# arduino_Uno_ref.net
KiCad netlist of a schematic drawn in EAGLE
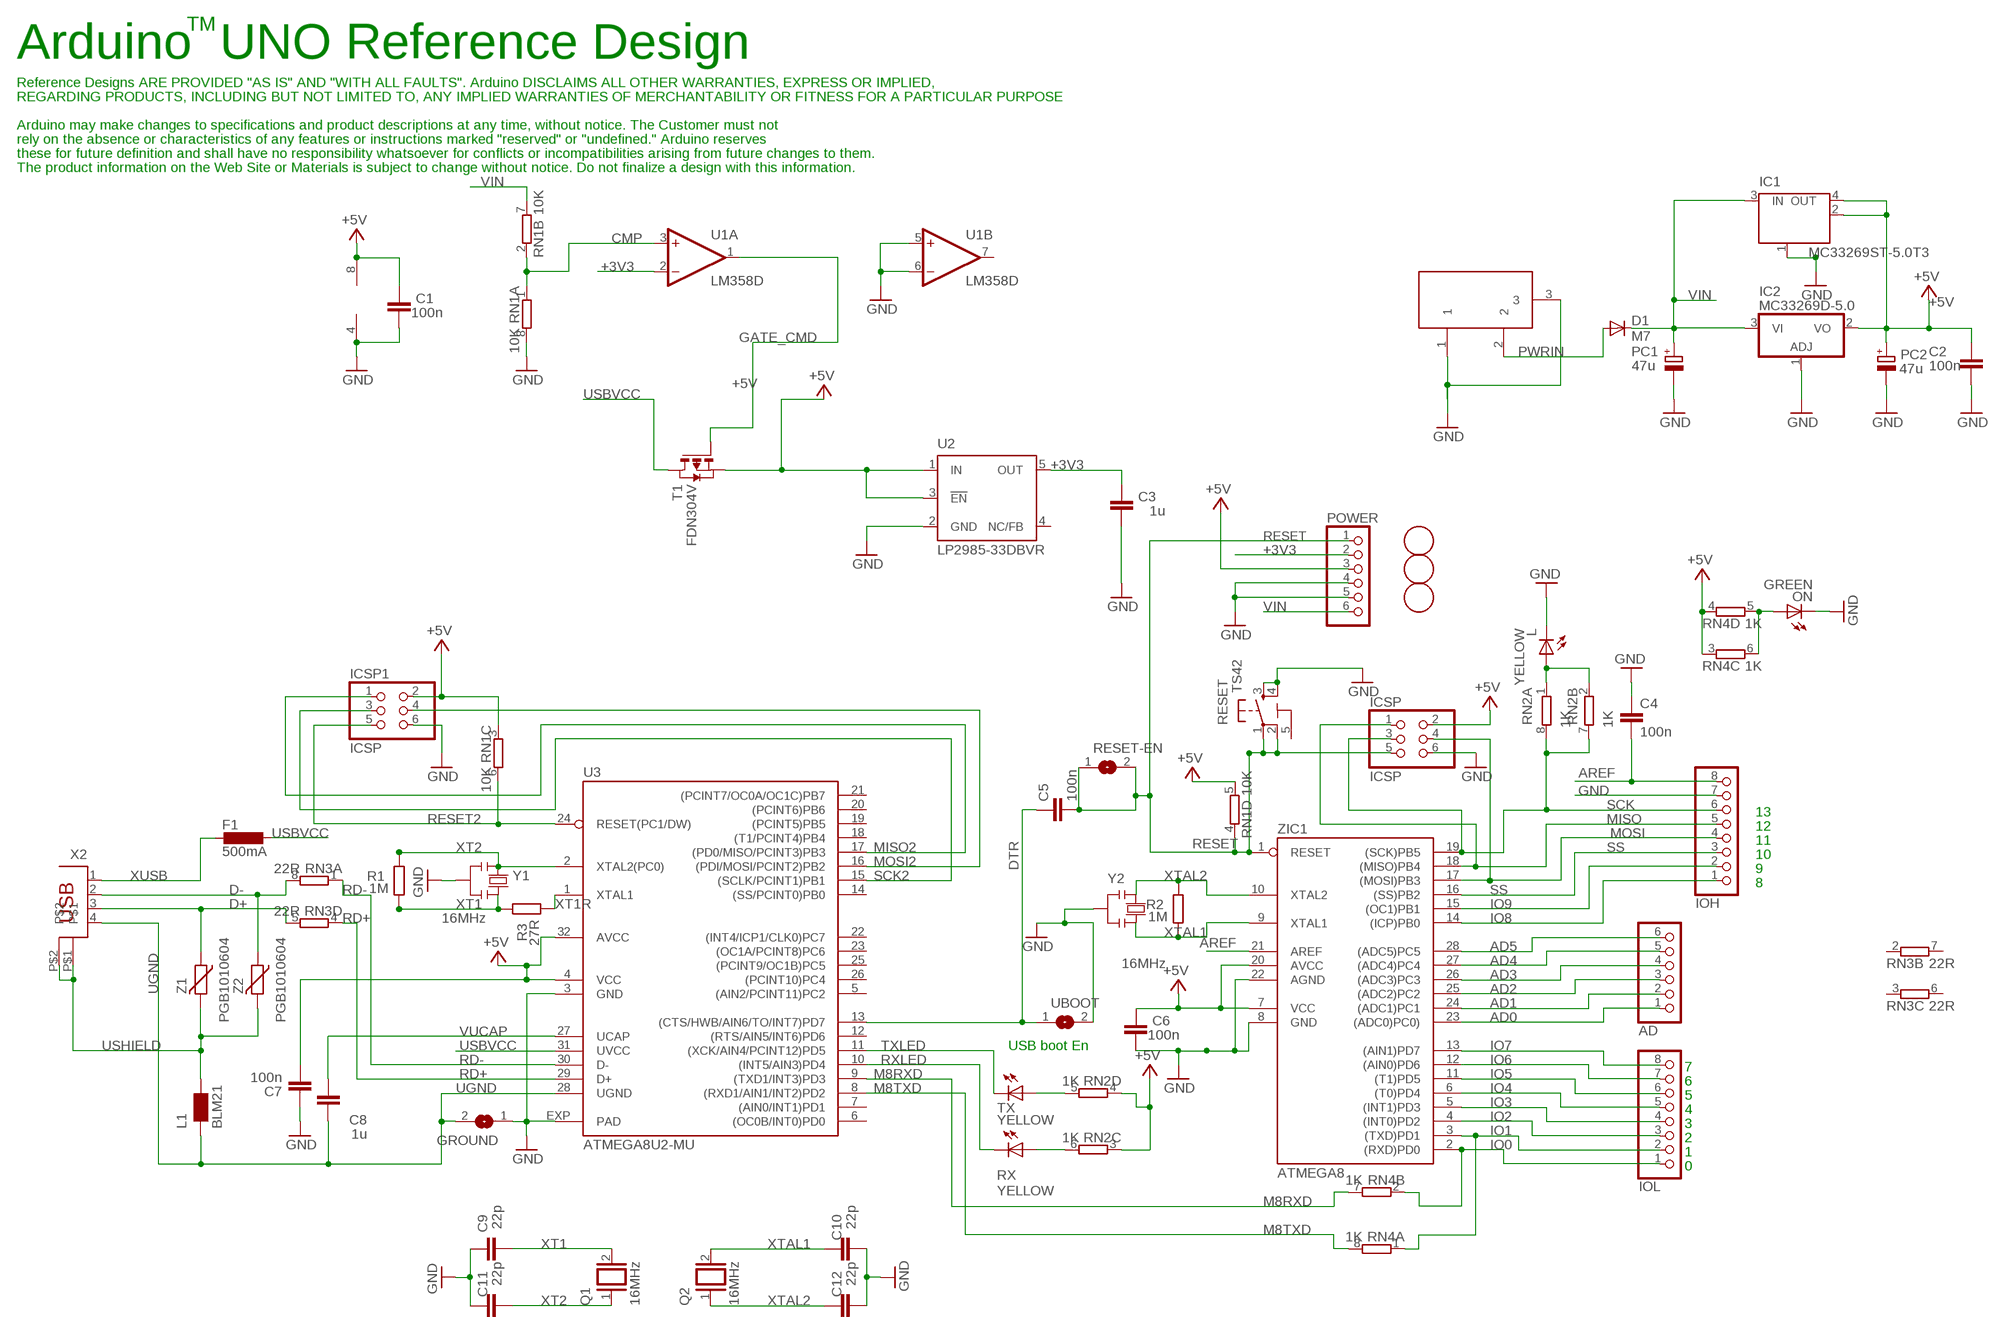
[diagram p0: schematic, sheet 1]

(export (version "E")
  (design (tool "Eeschema 10.0.6"))
  (components
    (comp (ref "AD")
      (value "PINHD-1X6")
      (footprint "eagle-import:1X06")
      (libsource (lib "eagle-import") (part "PINHD-1X6"))
    )
    (comp (ref "C1")
      (value "100n")
      (footprint "eagle-import:C0603-ROUND")
      (libsource (lib "eagle-import") (part "C-EU0603-RND"))
    )
    (comp (ref "C2")
      (value "100n")
      (footprint "eagle-import:C0603-ROUND")
      (libsource (lib "eagle-import") (part "C-EU0603-RND"))
    )
    (comp (ref "C3")
      (value "1u")
      (footprint "eagle-import:C0603-ROUND")
      (libsource (lib "eagle-import") (part "C-EU0603-RND"))
    )
    (comp (ref "C4")
      (value "100n")
      (footprint "eagle-import:C0603-ROUND")
      (libsource (lib "eagle-import") (part "C-EU0603-RND"))
    )
    (comp (ref "C5")
      (value "100n")
      (footprint "eagle-import:C0603-ROUND")
      (libsource (lib "eagle-import") (part "C-EU0603-RND"))
    )
    (comp (ref "C6")
      (value "100n")
      (footprint "eagle-import:C0603-ROUND")
      (libsource (lib "eagle-import") (part "C-EU0603-RND"))
    )
    (comp (ref "C7")
      (value "100n")
      (footprint "eagle-import:C0603-ROUND")
      (libsource (lib "eagle-import") (part "C-EU0603-RND"))
    )
    (comp (ref "C8")
      (value "1u")
      (footprint "eagle-import:C0603-ROUND")
      (libsource (lib "eagle-import") (part "C-EU0603-RND"))
    )
    (comp (ref "C9")
      (value "22p")
      (footprint "eagle-import:C0603-ROUND")
      (libsource (lib "eagle-import") (part "C-EU0603-RND"))
    )
    (comp (ref "C10")
      (value "22p")
      (footprint "eagle-import:C0603-ROUND")
      (libsource (lib "eagle-import") (part "C-EU0603-RND"))
    )
    (comp (ref "C11")
      (value "22p")
      (footprint "eagle-import:C0603-ROUND")
      (libsource (lib "eagle-import") (part "C-EU0603-RND"))
    )
    (comp (ref "C12")
      (value "22p")
      (footprint "eagle-import:C0603-ROUND")
      (libsource (lib "eagle-import") (part "C-EU0603-RND"))
    )
    (comp (ref "D1")
      (value "M7")
      (footprint "eagle-import:SMB")
      (libsource (lib "eagle-import") (part "DIODE-SMB"))
    )
    (comp (ref "F1")
      (value "500mA")
      (footprint "eagle-import:L1812")
      (libsource (lib "eagle-import") (part "L-EUL1812"))
    )
    (comp (ref "GROUND")
      (value "SJ")
      (footprint "eagle-import:SJ")
      (libsource (lib "eagle-import") (part "SJ"))
    )
    (comp (ref "IC1")
      (value "MC33269ST-5.0T3")
      (footprint "eagle-import:SOT223")
      (libsource (lib "eagle-import") (part "MC33269ST-3.3T3"))
    )
    (comp (ref "IC2")
      (value "MC33269D-5.0")
      (footprint "eagle-import:DPACK")
      (libsource (lib "eagle-import") (part "MC33269?D-5.0"))
    )
    (comp (ref "ICSP")
      (value "ICSP")
      (footprint "eagle-import:2X03")
      (libsource (lib "eagle-import") (part "PINHD-2X3"))
    )
    (comp (ref "ICSP1")
      (value "ICSP")
      (footprint "eagle-import:2X03")
      (libsource (lib "eagle-import") (part "PINHD-2X3"))
    )
    (comp (ref "IOH")
      (value "PINHD-1X8")
      (footprint "eagle-import:1X08")
      (libsource (lib "eagle-import") (part "PINHD-1X8"))
    )
    (comp (ref "IOL")
      (value "PINHD-1X8")
      (footprint "eagle-import:1X08")
      (libsource (lib "eagle-import") (part "PINHD-1X8"))
    )
    (comp (ref "L")
      (value "YELLOW")
      (footprint "eagle-import:CHIP-LED0805")
      (libsource (lib "eagle-import") (part "LEDCHIP-LED0805"))
    )
    (comp (ref "L1")
      (value "BLM21")
      (footprint "eagle-import:0805")
      (libsource (lib "eagle-import") (part "WE-CBF_0805"))
    )
    (comp (ref "ON")
      (value "GREEN")
      (footprint "eagle-import:CHIP-LED0805")
      (libsource (lib "eagle-import") (part "LEDCHIP-LED0805"))
    )
    (comp (ref "PC1")
      (value "47u")
      (footprint "eagle-import:PANASONIC_D")
      (libsource (lib "eagle-import") (part "CPOL-EUD"))
    )
    (comp (ref "PC2")
      (value "47u")
      (footprint "eagle-import:PANASONIC_D")
      (libsource (lib "eagle-import") (part "CPOL-EUD"))
    )
    (comp (ref "POWER")
      (value "PINHD-1X6")
      (footprint "eagle-import:1X06")
      (libsource (lib "eagle-import") (part "PINHD-1X6"))
    )
    (comp (ref "Q1")
      (value "16MHz")
      (footprint "eagle-import:QS")
      (libsource (lib "eagle-import") (part "XTAL/S"))
    )
    (comp (ref "Q2")
      (value "16MHz")
      (footprint "eagle-import:QS")
      (libsource (lib "eagle-import") (part "XTAL/S"))
    )
    (comp (ref "R1")
      (value "1M")
      (footprint "eagle-import:R0603-ROUND")
      (libsource (lib "eagle-import") (part "R-EU_R0603"))
    )
    (comp (ref "R2")
      (value "1M")
      (footprint "eagle-import:R0603-ROUND")
      (libsource (lib "eagle-import") (part "R-EU_R0603"))
    )
    (comp (ref "R3")
      (value "27R")
      (footprint "eagle-import:R0603-ROUND")
      (libsource (lib "eagle-import") (part "R-EU_R0603"))
    )
    (comp (ref "RESET")
      (value "TS42")
      (footprint "eagle-import:TS42")
      (libsource (lib "eagle-import") (part "TS42"))
    )
    (comp (ref "RESET-EN")
      (value "SJ")
      (footprint "eagle-import:SJ")
      (libsource (lib "eagle-import") (part "SJ"))
    )
    (comp (ref "RN1")
      (value "10K")
      (footprint "eagle-import:CAY16")
      (libsource (lib "eagle-import") (part "4R-NCAY16"))
    )
    (comp (ref "RN2")
      (value "1K")
      (footprint "eagle-import:CAY16")
      (libsource (lib "eagle-import") (part "4R-NCAY16"))
    )
    (comp (ref "RN3")
      (value "22R")
      (footprint "eagle-import:CAY16")
      (libsource (lib "eagle-import") (part "4R-NCAY16"))
    )
    (comp (ref "RN4")
      (value "1K")
      (footprint "eagle-import:CAY16")
      (libsource (lib "eagle-import") (part "4R-NCAY16"))
    )
    (comp (ref "RX")
      (value "YELLOW")
      (footprint "eagle-import:CHIP-LED0805")
      (libsource (lib "eagle-import") (part "LEDCHIP-LED0805"))
    )
    (comp (ref "T1")
      (value "FDN304V")
      (footprint "eagle-import:SOT-23")
      (libsource (lib "eagle-import") (part "PMOSSOT23"))
    )
    (comp (ref "TX")
      (value "YELLOW")
      (footprint "eagle-import:CHIP-LED0805")
      (libsource (lib "eagle-import") (part "LEDCHIP-LED0805"))
    )
    (comp (ref "U$3")
      (value "FIDUCIALMOUNT")
      (footprint "eagle-import:FIDUCIA-MOUNT")
      (libsource (lib "eagle-import") (part "FIDUCIALMOUNT"))
    )
    (comp (ref "U$4")
      (value "FIDUCIALMOUNT")
      (footprint "eagle-import:FIDUCIA-MOUNT")
      (libsource (lib "eagle-import") (part "FIDUCIALMOUNT"))
    )
    (comp (ref "U$6")
      (value "FIDUCIALMOUNT")
      (footprint "eagle-import:FIDUCIA-MOUNT")
      (libsource (lib "eagle-import") (part "FIDUCIALMOUNT"))
    )
    (comp (ref "U1")
      (value "LM358D")
      (footprint "eagle-import:SO08")
      (libsource (lib "eagle-import") (part "LM358D"))
    )
    (comp (ref "U2")
      (value "LP2985-33DBVR")
      (footprint "eagle-import:SOT23-DBV")
      (libsource (lib "eagle-import") (part "TPS77033"))
    )
    (comp (ref "U3")
      (value "ATMEGA8U2-MU")
      (footprint "eagle-import:QFN32")
      (libsource (lib "eagle-import") (part "ATMEGA8U2-MU"))
    )
    (comp (ref "UBOOT")
      (value "SJ")
      (footprint "eagle-import:SJ")
      (libsource (lib "eagle-import") (part "SJ"))
    )
    (comp (ref "X1")
      (value "DC21MMX")
      (footprint "eagle-import:DC-21MM")
      (libsource (lib "eagle-import") (part "DC21MMX"))
    )
    (comp (ref "X2")
      (value "PN61729")
      (footprint "eagle-import:PN61729")
      (libsource (lib "eagle-import") (part "PN61729"))
    )
    (comp (ref "Y1")
      (value "16MHz")
      (footprint "eagle-import:RESONATOR")
      (libsource (lib "eagle-import") (part "RESONATORMU"))
    )
    (comp (ref "Y2")
      (value "16MHz")
      (footprint "eagle-import:RESONATOR")
      (libsource (lib "eagle-import") (part "RESONATORMU"))
    )
    (comp (ref "Z1")
      (value "PGB1010604")
      (footprint "eagle-import:CT_CN0603")
      (libsource (lib "eagle-import") (part "VARISTORCN0603"))
    )
    (comp (ref "Z2")
      (value "PGB1010604")
      (footprint "eagle-import:CT_CN0603")
      (libsource (lib "eagle-import") (part "VARISTORCN0603"))
    )
    (comp (ref "ZIC1")
      (value "ATMEGA8")
      (footprint "eagle-import:DIL28-3")
      (libsource (lib "eagle-import") (part "AT90S4433P"))
    )
  )
  (nets
    (net (code "1") (name "+5V") (class "Default")
      (node (ref "C1") (pin "2") (pinfunction "2_2") (pintype "passive"))
      (node (ref "C2") (pin "2") (pinfunction "2_2") (pintype "passive"))
      (node (ref "C6") (pin "2") (pinfunction "2_2") (pintype "passive"))
      (node (ref "C7") (pin "1") (pinfunction "1_1") (pintype "passive"))
      (node (ref "IC1") (pin "2") (pinfunction "OUT_2") (pintype "passive"))
      (node (ref "IC1") (pin "4") (pinfunction "OUT_4") (pintype "passive"))
      (node (ref "IC2") (pin "2") (pinfunction "VO_2") (pintype "passive"))
      (node (ref "ICSP") (pin "2") (pinfunction "2_2") (pintype "passive"))
      (node (ref "ICSP1") (pin "2") (pinfunction "2_2") (pintype "passive"))
      (node (ref "PC2") (pin "+") (pinfunction "+_+") (pintype "passive"))
      (node (ref "POWER") (pin "3") (pinfunction "3_3") (pintype "passive"))
      (node (ref "RN1") (pin "3") (pinfunction "1_3") (pintype "passive"))
      (node (ref "RN1") (pin "5") (pinfunction "2_5") (pintype "passive"))
      (node (ref "RN2") (pin "3") (pinfunction "1_3") (pintype "passive"))
      (node (ref "RN2") (pin "4") (pinfunction "1_4") (pintype "passive"))
      (node (ref "RN4") (pin "3") (pinfunction "1_3") (pintype "passive"))
      (node (ref "RN4") (pin "4") (pinfunction "1_4") (pintype "passive"))
      (node (ref "T1") (pin "2") (pinfunction "S_2") (pintype "passive"))
      (node (ref "U1") (pin "8") (pinfunction "V+_8") (pintype "power_in"))
      (node (ref "U2") (pin "1") (pinfunction "IN_1") (pintype "input"))
      (node (ref "U2") (pin "3") (pinfunction "~{EN}_3") (pintype "input"))
      (node (ref "U3") (pin "32") (pinfunction "AVCC_32") (pintype "power_in"))
      (node (ref "U3") (pin "4") (pinfunction "VCC_4") (pintype "power_in"))
      (node (ref "ZIC1") (pin "20") (pinfunction "AVCC_20") (pintype "power_in"))
      (node (ref "ZIC1") (pin "7") (pinfunction "VCC_7") (pintype "power_in"))
    )
    (net (code "2") (name "/+3V3") (class "Default")
      (node (ref "C3") (pin "2") (pinfunction "2_2") (pintype "passive"))
      (node (ref "POWER") (pin "2") (pinfunction "2_2") (pintype "passive"))
      (node (ref "U1") (pin "2") (pinfunction "-IN_2") (pintype "input"))
      (node (ref "U2") (pin "5") (pinfunction "OUT_5") (pintype "passive"))
    )
    (net (code "3") (name "/5-GND") (class "Default")
      (node (ref "RESET") (pin "5") (pinfunction "5-GND_5") (pintype "power_in"))
    )
    (net (code "4") (name "/AD0") (class "Default")
      (node (ref "AD") (pin "1") (pinfunction "1_1") (pintype "passive"))
      (node (ref "ZIC1") (pin "23") (pinfunction "(ADC0)PC0)_23") (pintype "bidirectional"))
    )
    (net (code "5") (name "/AD1") (class "Default")
      (node (ref "AD") (pin "2") (pinfunction "2_2") (pintype "passive"))
      (node (ref "ZIC1") (pin "24") (pinfunction "(ADC1)PC1_24") (pintype "bidirectional"))
    )
    (net (code "6") (name "/AD2") (class "Default")
      (node (ref "AD") (pin "3") (pinfunction "3_3") (pintype "passive"))
      (node (ref "ZIC1") (pin "25") (pinfunction "(ADC2)PC2_25") (pintype "bidirectional"))
    )
    (net (code "7") (name "/AD3") (class "Default")
      (node (ref "AD") (pin "4") (pinfunction "4_4") (pintype "passive"))
      (node (ref "ZIC1") (pin "26") (pinfunction "(ADC3)PC3_26") (pintype "bidirectional"))
    )
    (net (code "8") (name "/AD4") (class "Default")
      (node (ref "AD") (pin "5") (pinfunction "5_5") (pintype "passive"))
      (node (ref "ZIC1") (pin "27") (pinfunction "(ADC4)PC4_27") (pintype "bidirectional"))
    )
    (net (code "9") (name "/AD5") (class "Default")
      (node (ref "AD") (pin "6") (pinfunction "6_6") (pintype "passive"))
      (node (ref "ZIC1") (pin "28") (pinfunction "(ADC5)PC5_28") (pintype "bidirectional"))
    )
    (net (code "10") (name "/AREF") (class "Default")
      (node (ref "C4") (pin "2") (pinfunction "2_2") (pintype "passive"))
      (node (ref "IOH") (pin "8") (pinfunction "8_8") (pintype "passive"))
      (node (ref "ZIC1") (pin "21") (pinfunction "AREF_21") (pintype "passive"))
    )
    (net (code "11") (name "/CMP") (class "Default")
      (node (ref "RN1") (pin "1") (pinfunction "1_1") (pintype "passive"))
      (node (ref "RN1") (pin "2") (pinfunction "1_2") (pintype "passive"))
      (node (ref "U1") (pin "3") (pinfunction "+IN_3") (pintype "input"))
    )
    (net (code "12") (name "/D+") (class "Default")
      (node (ref "RN3") (pin "5") (pinfunction "2_5") (pintype "passive"))
      (node (ref "X2") (pin "3") (pinfunction "3_3") (pintype "bidirectional"))
      (node (ref "Z1") (pin "1") (pinfunction "1_1") (pintype "passive"))
    )
    (net (code "13") (name "/D-") (class "Default")
      (node (ref "RN3") (pin "8") (pinfunction "2_8") (pintype "passive"))
      (node (ref "X2") (pin "2") (pinfunction "2_2") (pintype "bidirectional"))
      (node (ref "Z2") (pin "1") (pinfunction "1_1") (pintype "passive"))
    )
    (net (code "14") (name "/DTR") (class "Default")
      (node (ref "C5") (pin "1") (pinfunction "1_1") (pintype "passive"))
      (node (ref "U3") (pin "13") (pinfunction "(CTS/HWB/AIN6/TO/INT7)PD7_13") (pintype "bidirectional"))
      (node (ref "UBOOT") (pin "1") (pinfunction "1_1") (pintype "passive"))
    )
    (net (code "15") (name "/GATE_CMD") (class "Default")
      (node (ref "T1") (pin "3") (pinfunction "G_3") (pintype "passive"))
      (node (ref "U1") (pin "1") (pinfunction "OUT_1") (pintype "output"))
    )
    (net (code "16") (name "/IO0") (class "Default")
      (node (ref "IOL") (pin "1") (pinfunction "1_1") (pintype "passive"))
      (node (ref "RN4") (pin "2") (pinfunction "1_2") (pintype "passive"))
      (node (ref "ZIC1") (pin "2") (pinfunction "(RXD)PD0_2") (pintype "bidirectional"))
    )
    (net (code "17") (name "/IO1") (class "Default")
      (node (ref "IOL") (pin "2") (pinfunction "2_2") (pintype "passive"))
      (node (ref "RN4") (pin "1") (pinfunction "1_1") (pintype "passive"))
      (node (ref "ZIC1") (pin "3") (pinfunction "(TXD)PD1_3") (pintype "bidirectional"))
    )
    (net (code "18") (name "/IO2") (class "Default")
      (node (ref "IOL") (pin "3") (pinfunction "3_3") (pintype "passive"))
      (node (ref "ZIC1") (pin "4") (pinfunction "(INT0)PD2_4") (pintype "bidirectional"))
    )
    (net (code "19") (name "/IO3") (class "Default")
      (node (ref "IOL") (pin "4") (pinfunction "4_4") (pintype "passive"))
      (node (ref "ZIC1") (pin "5") (pinfunction "(INT1)PD3_5") (pintype "bidirectional"))
    )
    (net (code "20") (name "/IO4") (class "Default")
      (node (ref "IOL") (pin "5") (pinfunction "5_5") (pintype "passive"))
      (node (ref "ZIC1") (pin "6") (pinfunction "(T0)PD4_6") (pintype "bidirectional"))
    )
    (net (code "21") (name "/IO5") (class "Default")
      (node (ref "IOL") (pin "6") (pinfunction "6_6") (pintype "passive"))
      (node (ref "ZIC1") (pin "11") (pinfunction "(T1)PD5_11") (pintype "bidirectional"))
    )
    (net (code "22") (name "/IO6") (class "Default")
      (node (ref "IOL") (pin "7") (pinfunction "7_7") (pintype "passive"))
      (node (ref "ZIC1") (pin "12") (pinfunction "(AIN0)PD6_12") (pintype "bidirectional"))
    )
    (net (code "23") (name "/IO7") (class "Default")
      (node (ref "IOL") (pin "8") (pinfunction "8_8") (pintype "passive"))
      (node (ref "ZIC1") (pin "13") (pinfunction "(AIN1)PD7_13") (pintype "bidirectional"))
    )
    (net (code "24") (name "/IO8") (class "Default")
      (node (ref "IOH") (pin "1") (pinfunction "1_1") (pintype "passive"))
      (node (ref "ZIC1") (pin "14") (pinfunction "(ICP)PB0_14") (pintype "bidirectional"))
    )
    (net (code "25") (name "/IO9") (class "Default")
      (node (ref "IOH") (pin "2") (pinfunction "2_2") (pintype "passive"))
      (node (ref "ZIC1") (pin "15") (pinfunction "(OC1)PB1_15") (pintype "bidirectional"))
    )
    (net (code "26") (name "/M8RXD") (class "Default")
      (node (ref "RN4") (pin "7") (pinfunction "2_7") (pintype "passive"))
      (node (ref "U3") (pin "9") (pinfunction "(TXD1/INT3)PD3_9") (pintype "bidirectional"))
    )
    (net (code "27") (name "/M8TXD") (class "Default")
      (node (ref "RN4") (pin "8") (pinfunction "2_8") (pintype "passive"))
      (node (ref "U3") (pin "8") (pinfunction "(RXD1/AIN1/INT2)PD2_8") (pintype "bidirectional"))
    )
    (net (code "28") (name "/MISO") (class "Default")
      (node (ref "ICSP") (pin "1") (pinfunction "1_1") (pintype "passive"))
      (node (ref "IOH") (pin "5") (pinfunction "5_5") (pintype "passive"))
      (node (ref "ZIC1") (pin "18") (pinfunction "(MISO)PB4_18") (pintype "bidirectional"))
    )
    (net (code "29") (name "/MISO2") (class "Default")
      (node (ref "ICSP1") (pin "1") (pinfunction "1_1") (pintype "passive"))
      (node (ref "U3") (pin "17") (pinfunction "(PD0/MISO/PCINT3)PB3_17") (pintype "bidirectional"))
    )
    (net (code "30") (name "/MOSI") (class "Default")
      (node (ref "ICSP") (pin "4") (pinfunction "4_4") (pintype "passive"))
      (node (ref "IOH") (pin "4") (pinfunction "4_4") (pintype "passive"))
      (node (ref "ZIC1") (pin "17") (pinfunction "(MOSI)PB3_17") (pintype "bidirectional"))
    )
    (net (code "31") (name "/MOSI2") (class "Default")
      (node (ref "ICSP1") (pin "4") (pinfunction "4_4") (pintype "passive"))
      (node (ref "U3") (pin "16") (pinfunction "(PDI/MOSI/PCINT2)PB2_16") (pintype "bidirectional"))
    )
    (net (code "32") (name "/PWRIN") (class "Default")
      (node (ref "D1") (pin "A") (pinfunction "A_A") (pintype "passive"))
      (node (ref "X1") (pin "2") (pinfunction "2_2") (pintype "power_in"))
    )
    (net (code "33") (name "/RD+") (class "Default")
      (node (ref "RN3") (pin "4") (pinfunction "1_4") (pintype "passive"))
      (node (ref "U3") (pin "29") (pinfunction "D+_29") (pintype "bidirectional"))
    )
    (net (code "34") (name "/RD-") (class "Default")
      (node (ref "RN3") (pin "1") (pinfunction "1_1") (pintype "passive"))
      (node (ref "U3") (pin "30") (pinfunction "D-_30") (pintype "bidirectional"))
    )
    (net (code "35") (name "/RESET") (class "Default")
      (node (ref "C5") (pin "2") (pinfunction "2_2") (pintype "passive"))
      (node (ref "ICSP") (pin "5") (pinfunction "5_5") (pintype "passive"))
      (node (ref "POWER") (pin "1") (pinfunction "1_1") (pintype "passive"))
      (node (ref "RESET") (pin "1") (pinfunction "1_1") (pintype "passive"))
      (node (ref "RESET") (pin "2") (pinfunction "2_2") (pintype "passive"))
      (node (ref "RESET-EN") (pin "1") (pinfunction "1_1") (pintype "passive"))
      (node (ref "RESET-EN") (pin "2") (pinfunction "2_2") (pintype "passive"))
      (node (ref "RN1") (pin "4") (pinfunction "1_4") (pintype "passive"))
      (node (ref "ZIC1") (pin "1") (pinfunction "RESET_1") (pintype "input"))
    )
    (net (code "36") (name "/RESET2") (class "Default")
      (node (ref "ICSP1") (pin "5") (pinfunction "5_5") (pintype "passive"))
      (node (ref "RN1") (pin "6") (pinfunction "2_6") (pintype "passive"))
      (node (ref "U3") (pin "24") (pinfunction "RESET(PC1/DW)_24") (pintype "input"))
    )
    (net (code "37") (name "/RXLED") (class "Default")
      (node (ref "RX") (pin "C") (pinfunction "C_C") (pintype "passive"))
      (node (ref "U3") (pin "10") (pinfunction "(INT5/AIN3)PD4_10") (pintype "bidirectional"))
    )
    (net (code "38") (name "/SCK") (class "Default")
      (node (ref "ICSP") (pin "3") (pinfunction "3_3") (pintype "passive"))
      (node (ref "IOH") (pin "6") (pinfunction "6_6") (pintype "passive"))
      (node (ref "RN2") (pin "7") (pinfunction "2_7") (pintype "passive"))
      (node (ref "RN2") (pin "8") (pinfunction "2_8") (pintype "passive"))
      (node (ref "ZIC1") (pin "19") (pinfunction "(SCK)PB5_19") (pintype "bidirectional"))
    )
    (net (code "39") (name "/SCK2") (class "Default")
      (node (ref "ICSP1") (pin "3") (pinfunction "3_3") (pintype "passive"))
      (node (ref "U3") (pin "15") (pinfunction "(SCLK/PCINT1)PB1_15") (pintype "bidirectional"))
    )
    (net (code "40") (name "/SS") (class "Default")
      (node (ref "IOH") (pin "3") (pinfunction "3_3") (pintype "passive"))
      (node (ref "ZIC1") (pin "16") (pinfunction "(SS)PB2_16") (pintype "bidirectional"))
    )
    (net (code "41") (name "/TXLED") (class "Default")
      (node (ref "TX") (pin "C") (pinfunction "C_C") (pintype "passive"))
      (node (ref "U3") (pin "11") (pinfunction "(XCK/AIN4/PCINT12)PD5_11") (pintype "bidirectional"))
    )
    (net (code "42") (name "/UGND") (class "Default")
      (node (ref "C8") (pin "2") (pinfunction "2_2") (pintype "passive"))
      (node (ref "GROUND") (pin "2") (pinfunction "2_2") (pintype "passive"))
      (node (ref "L1") (pin "1") (pinfunction "1_1") (pintype "passive"))
      (node (ref "U3") (pin "28") (pinfunction "UGND_28") (pintype "power_in"))
      (node (ref "X2") (pin "4") (pinfunction "4_4") (pintype "bidirectional"))
    )
    (net (code "43") (name "/USBVCC") (class "Default")
      (node (ref "F1") (pin "1") (pinfunction "1_1") (pintype "passive"))
      (node (ref "T1") (pin "1") (pinfunction "D_1") (pintype "passive"))
      (node (ref "U3") (pin "31") (pinfunction "UVCC_31") (pintype "power_in"))
    )
    (net (code "44") (name "/USHIELD") (class "Default")
      (node (ref "L1") (pin "2") (pinfunction "2_2") (pintype "passive"))
      (node (ref "X2") (pin "P$1") (pinfunction "P$1_P$1") (pintype "bidirectional"))
      (node (ref "X2") (pin "P$2") (pinfunction "P$2_P$2") (pintype "bidirectional"))
      (node (ref "Z1") (pin "2") (pinfunction "2_2") (pintype "passive"))
      (node (ref "Z2") (pin "2") (pinfunction "2_2") (pintype "passive"))
    )
    (net (code "45") (name "/VIN") (class "Default")
      (node (ref "D1") (pin "C") (pinfunction "C_C") (pintype "passive"))
      (node (ref "IC1") (pin "3") (pinfunction "IN_3") (pintype "input"))
      (node (ref "IC2") (pin "3") (pinfunction "VI_3") (pintype "input"))
      (node (ref "PC1") (pin "+") (pinfunction "+_+") (pintype "passive"))
      (node (ref "POWER") (pin "6") (pinfunction "6_6") (pintype "passive"))
      (node (ref "RN1") (pin "7") (pinfunction "2_7") (pintype "passive"))
    )
    (net (code "46") (name "/VUCAP") (class "Default")
      (node (ref "C8") (pin "1") (pinfunction "1_1") (pintype "passive"))
      (node (ref "U3") (pin "27") (pinfunction "UCAP_27") (pintype "passive"))
    )
    (net (code "47") (name "/XT1") (class "Default")
      (node (ref "C9") (pin "1") (pinfunction "1_1") (pintype "passive"))
      (node (ref "Q1") (pin "2") (pinfunction "2_2") (pintype "passive"))
      (node (ref "R1") (pin "1") (pinfunction "1_1") (pintype "passive"))
      (node (ref "R3") (pin "2") (pinfunction "2_2") (pintype "passive"))
      (node (ref "Y1") (pin "3") (pinfunction "3_3") (pintype "passive"))
    )
    (net (code "48") (name "/XT1R") (class "Default")
      (node (ref "R3") (pin "1") (pinfunction "1_1") (pintype "passive"))
      (node (ref "U3") (pin "1") (pinfunction "XTAL1_1") (pintype "bidirectional"))
    )
    (net (code "49") (name "/XT2") (class "Default")
      (node (ref "C11") (pin "1") (pinfunction "1_1") (pintype "passive"))
      (node (ref "Q1") (pin "1") (pinfunction "1_1") (pintype "passive"))
      (node (ref "R1") (pin "2") (pinfunction "2_2") (pintype "passive"))
      (node (ref "U3") (pin "2") (pinfunction "XTAL2(PC0)_2") (pintype "bidirectional"))
      (node (ref "Y1") (pin "1") (pinfunction "1_1") (pintype "passive"))
    )
    (net (code "50") (name "/XTAL1") (class "Default")
      (node (ref "C10") (pin "2") (pinfunction "2_2") (pintype "passive"))
      (node (ref "Q2") (pin "2") (pinfunction "2_2") (pintype "passive"))
      (node (ref "R2") (pin "1") (pinfunction "1_1") (pintype "passive"))
      (node (ref "Y2") (pin "3") (pinfunction "3_3") (pintype "passive"))
      (node (ref "ZIC1") (pin "9") (pinfunction "XTAL1_9") (pintype "bidirectional"))
    )
    (net (code "51") (name "/XTAL2") (class "Default")
      (node (ref "C12") (pin "2") (pinfunction "2_2") (pintype "passive"))
      (node (ref "Q2") (pin "1") (pinfunction "1_1") (pintype "passive"))
      (node (ref "R2") (pin "2") (pinfunction "2_2") (pintype "passive"))
      (node (ref "Y2") (pin "1") (pinfunction "1_1") (pintype "passive"))
      (node (ref "ZIC1") (pin "10") (pinfunction "XTAL2_10") (pintype "bidirectional"))
    )
    (net (code "52") (name "/XUSB") (class "Default")
      (node (ref "F1") (pin "2") (pinfunction "2_2") (pintype "passive"))
      (node (ref "X2") (pin "1") (pinfunction "1_1") (pintype "bidirectional"))
    )
    (net (code "53") (name "GND") (class "Default")
      (node (ref "C1") (pin "1") (pinfunction "1_1") (pintype "passive"))
      (node (ref "C10") (pin "1") (pinfunction "1_1") (pintype "passive"))
      (node (ref "C11") (pin "2") (pinfunction "2_2") (pintype "passive"))
      (node (ref "C12") (pin "1") (pinfunction "1_1") (pintype "passive"))
      (node (ref "C2") (pin "1") (pinfunction "1_1") (pintype "passive"))
      (node (ref "C3") (pin "1") (pinfunction "1_1") (pintype "passive"))
      (node (ref "C4") (pin "1") (pinfunction "1_1") (pintype "passive"))
      (node (ref "C6") (pin "1") (pinfunction "1_1") (pintype "passive"))
      (node (ref "C7") (pin "2") (pinfunction "2_2") (pintype "passive"))
      (node (ref "C9") (pin "2") (pinfunction "2_2") (pintype "passive"))
      (node (ref "GROUND") (pin "1") (pinfunction "1_1") (pintype "passive"))
      (node (ref "IC1") (pin "1") (pinfunction "GND/ADJ_1") (pintype "input"))
      (node (ref "IC2") (pin "1") (pinfunction "ADJ_1") (pintype "input"))
      (node (ref "ICSP") (pin "6") (pinfunction "6_6") (pintype "passive"))
      (node (ref "ICSP1") (pin "6") (pinfunction "6_6") (pintype "passive"))
      (node (ref "IOH") (pin "7") (pinfunction "7_7") (pintype "passive"))
      (node (ref "L") (pin "C") (pinfunction "C_C") (pintype "passive"))
      (node (ref "ON") (pin "C") (pinfunction "C_C") (pintype "passive"))
      (node (ref "PC1") (pin "-") (pinfunction "-_-") (pintype "passive"))
      (node (ref "PC2") (pin "-") (pinfunction "-_-") (pintype "passive"))
      (node (ref "POWER") (pin "4") (pinfunction "4_4") (pintype "passive"))
      (node (ref "POWER") (pin "5") (pinfunction "5_5") (pintype "passive"))
      (node (ref "RESET") (pin "3") (pinfunction "3_3") (pintype "passive"))
      (node (ref "RESET") (pin "4") (pinfunction "4_4") (pintype "passive"))
      (node (ref "RN1") (pin "8") (pinfunction "2_8") (pintype "passive"))
      (node (ref "U1") (pin "4") (pinfunction "V-_4") (pintype "power_in"))
      (node (ref "U1") (pin "5") (pinfunction "+IN_5") (pintype "input"))
      (node (ref "U1") (pin "6") (pinfunction "-IN_6") (pintype "input"))
      (node (ref "U2") (pin "2") (pinfunction "GND_2") (pintype "power_in"))
      (node (ref "U3") (pin "3") (pinfunction "GND_3") (pintype "power_in"))
      (node (ref "U3") (pin "EXP") (pinfunction "PAD_EXP") (pintype "power_in"))
      (node (ref "UBOOT") (pin "2") (pinfunction "2_2") (pintype "passive"))
      (node (ref "X1") (pin "1") (pinfunction "1_1") (pintype "power_in"))
      (node (ref "X1") (pin "3") (pinfunction "3_3") (pintype "power_in"))
      (node (ref "Y1") (pin "2") (pinfunction "2_2") (pintype "passive"))
      (node (ref "Y2") (pin "2") (pinfunction "2_2") (pintype "passive"))
      (node (ref "ZIC1") (pin "22") (pinfunction "AGND_22") (pintype "power_in"))
      (node (ref "ZIC1") (pin "8") (pinfunction "GND_8") (pintype "power_in"))
    )
    (net (code "54") (name "Net-(RN2B-1)") (class "Default")
      (node (ref "L") (pin "A") (pinfunction "A_A") (pintype "passive"))
      (node (ref "RN2") (pin "1") (pinfunction "1_1") (pintype "passive"))
      (node (ref "RN2") (pin "2") (pinfunction "1_2") (pintype "passive"))
    )
    (net (code "55") (name "Net-(RN2C-2)") (class "Default")
      (node (ref "RN2") (pin "6") (pinfunction "2_6") (pintype "passive"))
      (node (ref "RX") (pin "A") (pinfunction "A_A") (pintype "passive"))
    )
    (net (code "56") (name "Net-(RN2D-2)") (class "Default")
      (node (ref "RN2") (pin "5") (pinfunction "2_5") (pintype "passive"))
      (node (ref "TX") (pin "A") (pinfunction "A_A") (pintype "passive"))
    )
    (net (code "57") (name "Net-(RN4C-2)") (class "Default")
      (node (ref "ON") (pin "A") (pinfunction "A_A") (pintype "passive"))
      (node (ref "RN4") (pin "5") (pinfunction "2_5") (pintype "passive"))
      (node (ref "RN4") (pin "6") (pinfunction "2_6") (pintype "passive"))
    )
    (net (code "58") (name "unconnected-(RN3B-1-Pad2)") (class "Default")
      (node (ref "RN3") (pin "2") (pinfunction "1_2") (pintype "passive"))
    )
    (net (code "59") (name "unconnected-(RN3B-2-Pad7)") (class "Default")
      (node (ref "RN3") (pin "7") (pinfunction "2_7") (pintype "passive"))
    )
    (net (code "60") (name "unconnected-(RN3C-1-Pad3)") (class "Default")
      (node (ref "RN3") (pin "3") (pinfunction "1_3") (pintype "passive"))
    )
    (net (code "61") (name "unconnected-(RN3C-2-Pad6)") (class "Default")
      (node (ref "RN3") (pin "6") (pinfunction "2_6") (pintype "passive"))
    )
    (net (code "62") (name "unconnected-(U1B-OUT-Pad7)") (class "Default")
      (node (ref "U1") (pin "7") (pinfunction "OUT_7") (pintype "output"))
    )
    (net (code "63") (name "unconnected-(U2-NC{slash}FB-Pad4)") (class "Default")
      (node (ref "U2") (pin "4") (pinfunction "NC/FB_4") (pintype "passive"))
    )
    (net (code "64") (name "unconnected-(U3-(AIN0{slash}INT1)PD1-Pad7)") (class "Default")
      (node (ref "U3") (pin "7") (pinfunction "(AIN0/INT1)PD1_7") (pintype "bidirectional"))
    )
    (net (code "65") (name "unconnected-(U3-(AIN2{slash}PCINT11)PC2-Pad5)") (class "Default")
      (node (ref "U3") (pin "5") (pinfunction "(AIN2/PCINT11)PC2_5") (pintype "bidirectional"))
    )
    (net (code "66") (name "unconnected-(U3-(INT4{slash}ICP1{slash}CLK0)PC7-Pad22)") (class "Default")
      (node (ref "U3") (pin "22") (pinfunction "(INT4/ICP1/CLK0)PC7_22") (pintype "bidirectional"))
    )
    (net (code "67") (name "unconnected-(U3-(OC0B{slash}INT0)PD0-Pad6)") (class "Default")
      (node (ref "U3") (pin "6") (pinfunction "(OC0B/INT0)PD0_6") (pintype "bidirectional"))
    )
    (net (code "68") (name "unconnected-(U3-(OC1A{slash}PCINT8)PC6-Pad23)") (class "Default")
      (node (ref "U3") (pin "23") (pinfunction "(OC1A/PCINT8)PC6_23") (pintype "bidirectional"))
    )
    (net (code "69") (name "unconnected-(U3-(PCINT5)PB5-Pad19)") (class "Default")
      (node (ref "U3") (pin "19") (pinfunction "(PCINT5)PB5_19") (pintype "bidirectional"))
    )
    (net (code "70") (name "unconnected-(U3-(PCINT6)PB6-Pad20)") (class "Default")
      (node (ref "U3") (pin "20") (pinfunction "(PCINT6)PB6_20") (pintype "bidirectional"))
    )
    (net (code "71") (name "unconnected-(U3-(PCINT7{slash}OC0A{slash}OC1C)PB7-Pad21)") (class "Default")
      (node (ref "U3") (pin "21") (pinfunction "(PCINT7/OC0A/OC1C)PB7_21") (pintype "bidirectional"))
    )
    (net (code "72") (name "unconnected-(U3-(PCINT9{slash}OC1B)PC5-Pad25)") (class "Default")
      (node (ref "U3") (pin "25") (pinfunction "(PCINT9/OC1B)PC5_25") (pintype "bidirectional"))
    )
    (net (code "73") (name "unconnected-(U3-(PCINT10)PC4-Pad26)") (class "Default")
      (node (ref "U3") (pin "26") (pinfunction "(PCINT10)PC4_26") (pintype "bidirectional"))
    )
    (net (code "74") (name "unconnected-(U3-(RTS{slash}AIN5{slash}INT6)PD6-Pad12)") (class "Default")
      (node (ref "U3") (pin "12") (pinfunction "(RTS/AIN5/INT6)PD6_12") (pintype "bidirectional"))
    )
    (net (code "75") (name "unconnected-(U3-(SS{slash}PCINT0)PB0-Pad14)") (class "Default")
      (node (ref "U3") (pin "14") (pinfunction "(SS/PCINT0)PB0_14") (pintype "bidirectional"))
    )
    (net (code "76") (name "unconnected-(U3-(T1{slash}PCINT4)PB4-Pad18)") (class "Default")
      (node (ref "U3") (pin "18") (pinfunction "(T1/PCINT4)PB4_18") (pintype "bidirectional"))
    )
  )
)
